# eth_10base-t1s_phy.net
KiCad netlist of a schematic drawn in Altium Designer
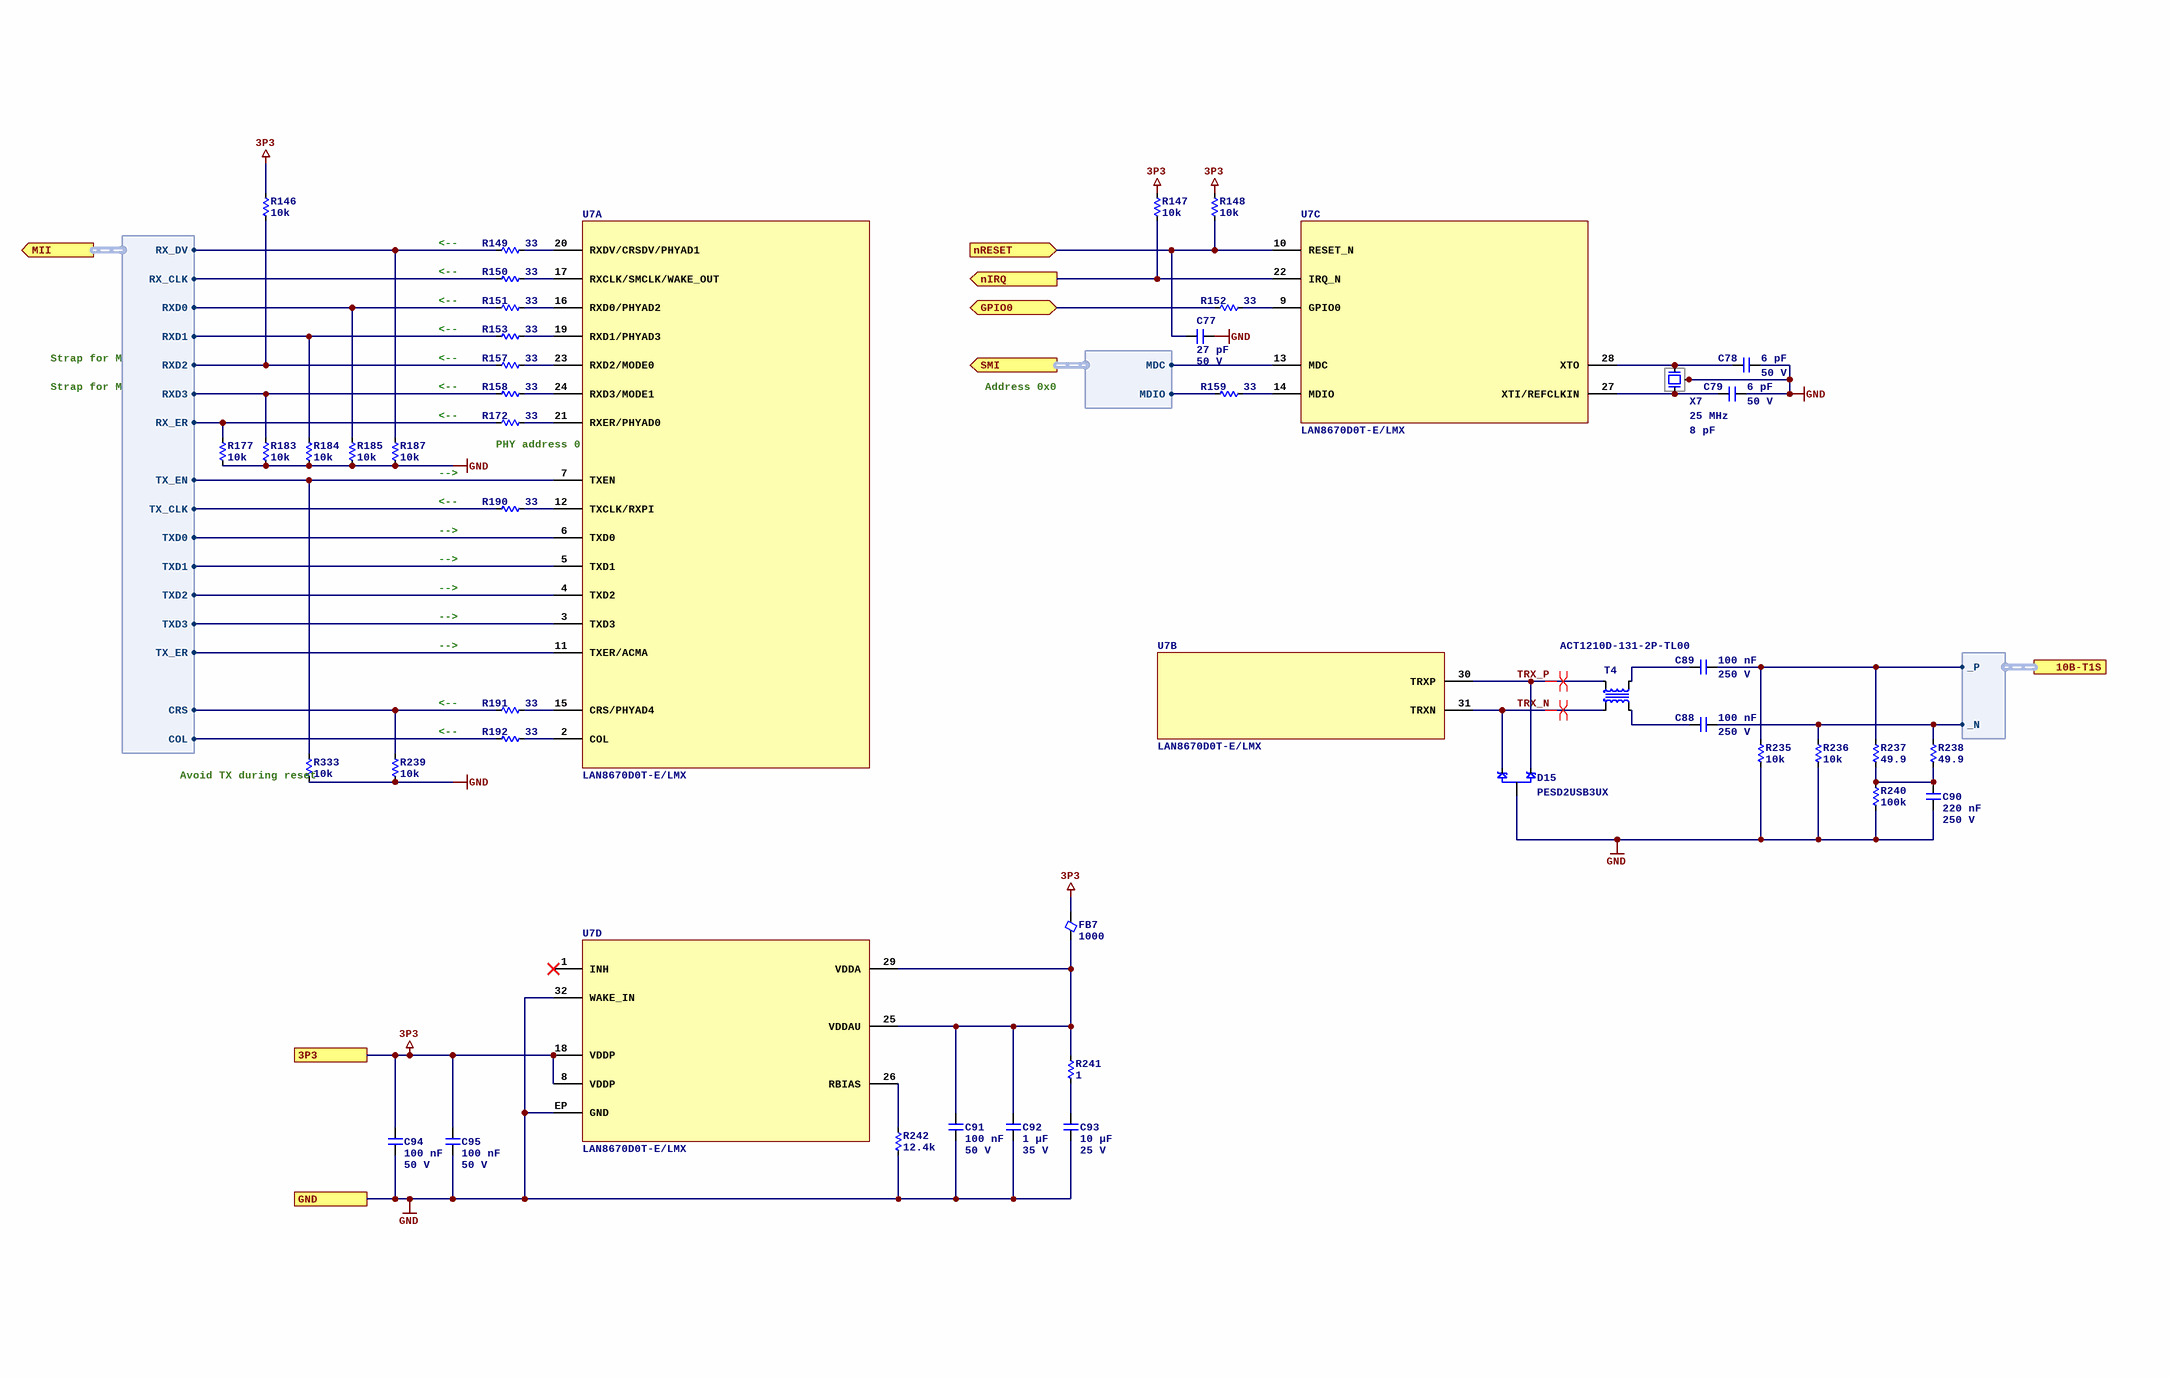
[diagram p0: eth_10base-t1s_phy.SchDoc]

(export (version "E")
  (design (tool "Eeschema 10.0.6"))
  (components
    (comp (ref "C77")
      (value "0402CG270J500NT")
      (footprint "C0402")
      (fields
        (field (name "CAPACITANCE") "27 pF")
        (field (name "MANUFACTURER") "FH(Guangdong Fenghua Advanced Tech)")
        (field (name "VOLTAGE RATING") "50 V")
      )
      (libsource (lib "database") (part "__template_cap"))
    )
    (comp (ref "C78")
      (value "0402CG6R0C500NT")
      (footprint "C0402")
      (fields
        (field (name "CAPACITANCE") "6 pF")
        (field (name "MANUFACTURER") "FH(Guangdong Fenghua Advanced Tech)")
        (field (name "VOLTAGE RATING") "50 V")
      )
      (libsource (lib "database") (part "__template_cap"))
    )
    (comp (ref "C79")
      (value "0402CG6R0C500NT")
      (footprint "C0402")
      (fields
        (field (name "CAPACITANCE") "6 pF")
        (field (name "MANUFACTURER") "FH(Guangdong Fenghua Advanced Tech)")
        (field (name "VOLTAGE RATING") "50 V")
      )
      (libsource (lib "database") (part "__template_cap"))
    )
    (comp (ref "C88")
      (value "FM31X104K251EEG")
      (footprint "C1206")
      (fields
        (field (name "CAPACITANCE") "100 nF")
        (field (name "MANUFACTURER") "PSA(Prosperity Dielectrics)")
        (field (name "VOLTAGE RATING") "250 V")
      )
      (libsource (lib "database") (part "__template_cap"))
    )
    (comp (ref "C89")
      (value "FM31X104K251EEG")
      (footprint "C1206")
      (fields
        (field (name "CAPACITANCE") "100 nF")
        (field (name "MANUFACTURER") "PSA(Prosperity Dielectrics)")
        (field (name "VOLTAGE RATING") "250 V")
      )
      (libsource (lib "database") (part "__template_cap"))
    )
    (comp (ref "C90")
      (value "FM32X224K251EEG")
      (footprint "C1210")
      (fields
        (field (name "CAPACITANCE") "220 nF")
        (field (name "MANUFACTURER") "PSA(Prosperity Dielectrics)")
        (field (name "VOLTAGE RATING") "250 V")
      )
      (libsource (lib "database") (part "__template_cap"))
    )
    (comp (ref "C91")
      (value "CL05B104KB54PNC")
      (footprint "C0402")
      (fields
        (field (name "CAPACITANCE") "100 nF")
        (field (name "MANUFACTURER") "Samsung Electro-Mechanics")
        (field (name "VOLTAGE RATING") "50 V")
      )
      (libsource (lib "database") (part "__template_cap"))
    )
    (comp (ref "C92")
      (value "GMK107AB7105KAHT")
      (footprint "C0603")
      (fields
        (field (name "CAPACITANCE") "1 µF")
        (field (name "MANUFACTURER") "Taiyo Yuden")
        (field (name "VOLTAGE RATING") "35 V")
      )
      (libsource (lib "database") (part "__template_cap"))
    )
    (comp (ref "C93")
      (value "CL21B106KAYQNNE")
      (footprint "C0805")
      (fields
        (field (name "CAPACITANCE") "10 µF")
        (field (name "MANUFACTURER") "Samsung Electro-Mechanics")
        (field (name "VOLTAGE RATING") "25 V")
      )
      (libsource (lib "database") (part "__template_cap"))
    )
    (comp (ref "C94")
      (value "CL05B104KB54PNC")
      (footprint "C0402")
      (fields
        (field (name "CAPACITANCE") "100 nF")
        (field (name "MANUFACTURER") "Samsung Electro-Mechanics")
        (field (name "VOLTAGE RATING") "50 V")
      )
      (libsource (lib "database") (part "__template_cap"))
    )
    (comp (ref "C95")
      (value "CL05B104KB54PNC")
      (footprint "C0402")
      (fields
        (field (name "CAPACITANCE") "100 nF")
        (field (name "MANUFACTURER") "Samsung Electro-Mechanics")
        (field (name "VOLTAGE RATING") "50 V")
      )
      (libsource (lib "database") (part "__template_cap"))
    )
    (comp (ref "D15")
      (value "PESD2USB3UX")
      (footprint "3SOT23")
      (description "DIODE ESD USB SOT-23")
      (fields (field (name "MANUFACTURER") "Nexperia USA Inc."))
      (libsource (lib "database") (part "PESD2USB3UX"))
    )
    (comp (ref "FB7")
      (value "HCB2012KF-102T10")
      (footprint "FB0805")
      (fields (field (name "MANUFACTURER") "TAI-TECH") (field (name "CURRENT RATING (MA)") "1000"))
      (libsource (lib "database") (part "__template_fb"))
    )
    (comp (ref "R146")
      (value "10k")
      (footprint "R0402")
      (fields
        (field (name "TOLERANCE") "1%")
        (field (name "MANUFACTURER PART NUMBER") "0402WGF1002TCE")
        (field (name "MANUFACTURER") "UNI-ROYAL(Uniroyal Elec)")
      )
      (libsource (lib "database") (part "__template_resistor"))
    )
    (comp (ref "R147")
      (value "10k")
      (footprint "R0402")
      (fields
        (field (name "TOLERANCE") "1%")
        (field (name "MANUFACTURER PART NUMBER") "0402WGF1002TCE")
        (field (name "MANUFACTURER") "UNI-ROYAL(Uniroyal Elec)")
      )
      (libsource (lib "database") (part "__template_resistor"))
    )
    (comp (ref "R148")
      (value "10k")
      (footprint "R0402")
      (fields
        (field (name "TOLERANCE") "1%")
        (field (name "MANUFACTURER PART NUMBER") "0402WGF1002TCE")
        (field (name "MANUFACTURER") "UNI-ROYAL(Uniroyal Elec)")
      )
      (libsource (lib "database") (part "__template_resistor"))
    )
    (comp (ref "R149")
      (value "33")
      (footprint "R0402")
      (fields
        (field (name "TOLERANCE") "1%")
        (field (name "MANUFACTURER PART NUMBER") "0402WGF330JTCE")
        (field (name "MANUFACTURER") "UNI-ROYAL(Uniroyal Elec)")
      )
      (libsource (lib "database") (part "__template_resistor"))
    )
    (comp (ref "R150")
      (value "33")
      (footprint "R0402")
      (fields
        (field (name "TOLERANCE") "1%")
        (field (name "MANUFACTURER PART NUMBER") "0402WGF330JTCE")
        (field (name "MANUFACTURER") "UNI-ROYAL(Uniroyal Elec)")
      )
      (libsource (lib "database") (part "__template_resistor"))
    )
    (comp (ref "R151")
      (value "33")
      (footprint "R0402")
      (fields
        (field (name "TOLERANCE") "1%")
        (field (name "MANUFACTURER PART NUMBER") "0402WGF330JTCE")
        (field (name "MANUFACTURER") "UNI-ROYAL(Uniroyal Elec)")
      )
      (libsource (lib "database") (part "__template_resistor"))
    )
    (comp (ref "R152")
      (value "33")
      (footprint "R0402")
      (fields
        (field (name "TOLERANCE") "1%")
        (field (name "MANUFACTURER PART NUMBER") "0402WGF330JTCE")
        (field (name "MANUFACTURER") "UNI-ROYAL(Uniroyal Elec)")
      )
      (libsource (lib "database") (part "__template_resistor"))
    )
    (comp (ref "R153")
      (value "33")
      (footprint "R0402")
      (fields
        (field (name "TOLERANCE") "1%")
        (field (name "MANUFACTURER PART NUMBER") "0402WGF330JTCE")
        (field (name "MANUFACTURER") "UNI-ROYAL(Uniroyal Elec)")
      )
      (libsource (lib "database") (part "__template_resistor"))
    )
    (comp (ref "R157")
      (value "33")
      (footprint "R0402")
      (fields
        (field (name "TOLERANCE") "1%")
        (field (name "MANUFACTURER PART NUMBER") "0402WGF330JTCE")
        (field (name "MANUFACTURER") "UNI-ROYAL(Uniroyal Elec)")
      )
      (libsource (lib "database") (part "__template_resistor"))
    )
    (comp (ref "R158")
      (value "33")
      (footprint "R0402")
      (fields
        (field (name "TOLERANCE") "1%")
        (field (name "MANUFACTURER PART NUMBER") "0402WGF330JTCE")
        (field (name "MANUFACTURER") "UNI-ROYAL(Uniroyal Elec)")
      )
      (libsource (lib "database") (part "__template_resistor"))
    )
    (comp (ref "R159")
      (value "33")
      (footprint "R0402")
      (fields
        (field (name "TOLERANCE") "1%")
        (field (name "MANUFACTURER PART NUMBER") "0402WGF330JTCE")
        (field (name "MANUFACTURER") "UNI-ROYAL(Uniroyal Elec)")
      )
      (libsource (lib "database") (part "__template_resistor"))
    )
    (comp (ref "R172")
      (value "33")
      (footprint "R0402")
      (fields
        (field (name "TOLERANCE") "1%")
        (field (name "MANUFACTURER PART NUMBER") "0402WGF330JTCE")
        (field (name "MANUFACTURER") "UNI-ROYAL(Uniroyal Elec)")
      )
      (libsource (lib "database") (part "__template_resistor"))
    )
    (comp (ref "R177")
      (value "10k")
      (footprint "R0402")
      (fields
        (field (name "TOLERANCE") "1%")
        (field (name "MANUFACTURER PART NUMBER") "0402WGF1002TCE")
        (field (name "MANUFACTURER") "UNI-ROYAL(Uniroyal Elec)")
      )
      (libsource (lib "database") (part "__template_resistor"))
    )
    (comp (ref "R183")
      (value "10k")
      (footprint "R0402")
      (fields
        (field (name "TOLERANCE") "1%")
        (field (name "MANUFACTURER PART NUMBER") "0402WGF1002TCE")
        (field (name "MANUFACTURER") "UNI-ROYAL(Uniroyal Elec)")
      )
      (libsource (lib "database") (part "__template_resistor"))
    )
    (comp (ref "R184")
      (value "10k")
      (footprint "R0402")
      (fields
        (field (name "TOLERANCE") "1%")
        (field (name "MANUFACTURER PART NUMBER") "0402WGF1002TCE")
        (field (name "MANUFACTURER") "UNI-ROYAL(Uniroyal Elec)")
      )
      (libsource (lib "database") (part "__template_resistor"))
    )
    (comp (ref "R185")
      (value "10k")
      (footprint "R0402")
      (fields
        (field (name "TOLERANCE") "1%")
        (field (name "MANUFACTURER PART NUMBER") "0402WGF1002TCE")
        (field (name "MANUFACTURER") "UNI-ROYAL(Uniroyal Elec)")
      )
      (libsource (lib "database") (part "__template_resistor"))
    )
    (comp (ref "R187")
      (value "10k")
      (footprint "R0402")
      (fields
        (field (name "TOLERANCE") "1%")
        (field (name "MANUFACTURER PART NUMBER") "0402WGF1002TCE")
        (field (name "MANUFACTURER") "UNI-ROYAL(Uniroyal Elec)")
      )
      (libsource (lib "database") (part "__template_resistor"))
    )
    (comp (ref "R190")
      (value "33")
      (footprint "R0402")
      (fields
        (field (name "TOLERANCE") "1%")
        (field (name "MANUFACTURER PART NUMBER") "0402WGF330JTCE")
        (field (name "MANUFACTURER") "UNI-ROYAL(Uniroyal Elec)")
      )
      (libsource (lib "database") (part "__template_resistor"))
    )
    (comp (ref "R191")
      (value "33")
      (footprint "R0402")
      (fields
        (field (name "TOLERANCE") "1%")
        (field (name "MANUFACTURER PART NUMBER") "0402WGF330JTCE")
        (field (name "MANUFACTURER") "UNI-ROYAL(Uniroyal Elec)")
      )
      (libsource (lib "database") (part "__template_resistor"))
    )
    (comp (ref "R192")
      (value "33")
      (footprint "R0402")
      (fields
        (field (name "TOLERANCE") "1%")
        (field (name "MANUFACTURER PART NUMBER") "0402WGF330JTCE")
        (field (name "MANUFACTURER") "UNI-ROYAL(Uniroyal Elec)")
      )
      (libsource (lib "database") (part "__template_resistor"))
    )
    (comp (ref "R235")
      (value "10k")
      (footprint "R1206")
      (fields
        (field (name "TOLERANCE") "1%")
        (field (name "MANUFACTURER PART NUMBER") "1206W4F1002T5E")
        (field (name "MANUFACTURER") "UNI-ROYAL(Uniroyal Elec)")
      )
      (libsource (lib "database") (part "__template_resistor"))
    )
    (comp (ref "R236")
      (value "10k")
      (footprint "R1206")
      (fields
        (field (name "TOLERANCE") "1%")
        (field (name "MANUFACTURER PART NUMBER") "1206W4F1002T5E")
        (field (name "MANUFACTURER") "UNI-ROYAL(Uniroyal Elec)")
      )
      (libsource (lib "database") (part "__template_resistor"))
    )
    (comp (ref "R237")
      (value "49.9")
      (footprint "R1206")
      (fields
        (field (name "TOLERANCE") "1%")
        (field (name "MANUFACTURER PART NUMBER") "FRC1206F49R9TS")
        (field (name "MANUFACTURER") "FOJAN")
      )
      (libsource (lib "database") (part "__template_resistor"))
    )
    (comp (ref "R238")
      (value "49.9")
      (footprint "R1206")
      (fields
        (field (name "TOLERANCE") "1%")
        (field (name "MANUFACTURER PART NUMBER") "FRC1206F49R9TS")
        (field (name "MANUFACTURER") "FOJAN")
      )
      (libsource (lib "database") (part "__template_resistor"))
    )
    (comp (ref "R239")
      (value "10k")
      (footprint "R0402")
      (fields
        (field (name "TOLERANCE") "1%")
        (field (name "MANUFACTURER PART NUMBER") "0402WGF1002TCE")
        (field (name "MANUFACTURER") "UNI-ROYAL(Uniroyal Elec)")
      )
      (libsource (lib "database") (part "__template_resistor"))
    )
    (comp (ref "R240")
      (value "100k")
      (footprint "R1206")
      (fields
        (field (name "TOLERANCE") "1%")
        (field (name "MANUFACTURER PART NUMBER") "1206W4F1003T5E")
        (field (name "MANUFACTURER") "UNI-ROYAL(Uniroyal Elec)")
      )
      (libsource (lib "database") (part "__template_resistor"))
    )
    (comp (ref "R241")
      (value "1")
      (footprint "R0402")
      (fields
        (field (name "TOLERANCE") "1%")
        (field (name "MANUFACTURER PART NUMBER") "CRCW04021R00FKED")
        (field (name "MANUFACTURER") "Vishay Intertech")
      )
      (libsource (lib "database") (part "__template_resistor"))
    )
    (comp (ref "R242")
      (value "12.4k")
      (footprint "R0402")
      (fields
        (field (name "TOLERANCE") "0.5%")
        (field (name "MANUFACTURER PART NUMBER") "0402WGD1242TCE")
        (field (name "MANUFACTURER") "UNI-ROYAL(Uniroyal Elec)")
      )
      (libsource (lib "database") (part "__template_resistor"))
    )
    (comp (ref "R333")
      (value "10k")
      (footprint "R0402")
      (fields
        (field (name "TOLERANCE") "1%")
        (field (name "MANUFACTURER PART NUMBER") "0402WGF1002TCE")
        (field (name "MANUFACTURER") "UNI-ROYAL(Uniroyal Elec)")
      )
      (libsource (lib "database") (part "__template_resistor"))
    )
    (comp (ref "T4")
      (value "ACT1210D-131-2P-TL00")
      (footprint "CHOKE_ACT1210D-131-2P-TL00")
      (description "130 µH @ 100 kHz 2 Line Common Mode Choke Surface Mount 6.7 kOhms @ 10 MHz 115mA DCR 3.5Ohm")
      (fields (field (name "MANUFACTURER") "TDK Corporation"))
      (libsource (lib "database") (part "__template_transformer"))
    )
    (comp (ref "U7")
      (value "LAN8670D0T-E/LMX")
      (footprint "QFN50P500X500X90-32N")
      (description "10BASE-T1S PHY WITH MII/RMII \"1/1 Transceiver Full, Half Ethernet 32-VQFN (5x5)\"")
      (fields (field (name "MANUFACTURER") "Microchip"))
      (libsource (lib "database") (part "LAN8670D0T-E/LMX"))
    )
    (comp (ref "X7")
      (value "ABM11W-25.0000MHZ-8-D1X-T3")
      (footprint "4_SMD_2.0X1.6MM")
      (description "25 MHz ±10ppm Crystal 8pF 50 Ohms 4-SMD, No Lead")
      (fields
        (field (name "MANUFACTURER") "Abracon LLC")
        (field (name "FREQUENCY") "25 MHz")
        (field (name "CAPACITANCE") "8 pF")
      )
      (libsource (lib "database") (part "__template_crystal_4pin"))
    )
  )
  (nets
    (net (code "4") (name "/COL") (class "Default") (node (ref "R192") (pin "2") (pintype "passive")))
    (net (code "5") (name "/CRS") (class "Default")
      (node (ref "R191") (pin "2") (pintype "passive"))
      (node (ref "R239") (pin "1") (pintype "passive"))
    )
    (net (code "6") (name "/GPIO0") (class "Default") (node (ref "R152") (pin "2") (pintype "passive")))
    (net (code "7") (name "/MDC") (class "Default")
      (node (ref "U7") (pin "13") (pinfunction "MDC_13") (pintype "passive"))
    )
    (net (code "8") (name "/MDIO") (class "Default") (node (ref "R159") (pin "2") (pintype "passive")))
    (net (code "9") (name "/RXD0") (class "Default")
      (node (ref "R151") (pin "2") (pintype "passive"))
      (node (ref "R185") (pin "1") (pintype "passive"))
    )
    (net (code "10") (name "/RXD1") (class "Default")
      (node (ref "R153") (pin "2") (pintype "passive"))
      (node (ref "R184") (pin "1") (pintype "passive"))
    )
    (net (code "11") (name "/RXD2") (class "Default")
      (node (ref "R146") (pin "2") (pintype "passive"))
      (node (ref "R157") (pin "2") (pintype "passive"))
    )
    (net (code "12") (name "/RXD3") (class "Default")
      (node (ref "R158") (pin "2") (pintype "passive"))
      (node (ref "R183") (pin "1") (pintype "passive"))
    )
    (net (code "13") (name "/RX_CLK") (class "Default") (node (ref "R150") (pin "2") (pintype "passive")))
    (net (code "14") (name "/RX_DV") (class "Default")
      (node (ref "R149") (pin "2") (pintype "passive"))
      (node (ref "R187") (pin "1") (pintype "passive"))
    )
    (net (code "15") (name "/RX_ER") (class "Default")
      (node (ref "R172") (pin "2") (pintype "passive"))
      (node (ref "R177") (pin "1") (pintype "passive"))
    )
    (net (code "16") (name "/TRX_N") (class "Default")
      (node (ref "D15") (pin "1") (pintype "passive"))
      (node (ref "T4") (pin "1") (pintype "passive"))
      (node (ref "U7") (pin "31") (pinfunction "TRXN_31") (pintype "passive"))
    )
    (net (code "17") (name "/TRX_P") (class "Default")
      (node (ref "D15") (pin "2") (pintype "passive"))
      (node (ref "T4") (pin "2") (pintype "passive"))
      (node (ref "U7") (pin "30") (pinfunction "TRXP_30") (pintype "passive"))
    )
    (net (code "18") (name "/TXD0") (class "Default")
      (node (ref "U7") (pin "6") (pinfunction "TXD0_6") (pintype "passive"))
    )
    (net (code "19") (name "/TXD1") (class "Default")
      (node (ref "U7") (pin "5") (pinfunction "TXD1_5") (pintype "passive"))
    )
    (net (code "20") (name "/TXD2") (class "Default")
      (node (ref "U7") (pin "4") (pinfunction "TXD2_4") (pintype "passive"))
    )
    (net (code "21") (name "/TXD3") (class "Default")
      (node (ref "U7") (pin "3") (pinfunction "TXD3_3") (pintype "passive"))
    )
    (net (code "22") (name "/TX_CLK") (class "Default") (node (ref "R190") (pin "2") (pintype "passive")))
    (net (code "23") (name "/TX_EN") (class "Default")
      (node (ref "R333") (pin "1") (pintype "passive"))
      (node (ref "U7") (pin "7") (pinfunction "TXEN_7") (pintype "passive"))
    )
    (net (code "24") (name "/TX_ER") (class "Default")
      (node (ref "U7") (pin "11") (pinfunction "TXER/ACMA_11") (pintype "passive"))
    )
    (net (code "25") (name "/_N") (class "Default")
      (node (ref "C88") (pin "2") (pintype "passive"))
      (node (ref "R236") (pin "1") (pintype "passive"))
      (node (ref "R238") (pin "1") (pintype "passive"))
    )
    (net (code "26") (name "/_P") (class "Default")
      (node (ref "C89") (pin "2") (pintype "passive"))
      (node (ref "R235") (pin "1") (pintype "passive"))
      (node (ref "R237") (pin "1") (pintype "passive"))
    )
    (net (code "27") (name "/nIRQ") (class "Default")
      (node (ref "R147") (pin "2") (pintype "passive"))
      (node (ref "U7") (pin "22") (pinfunction "IRQ_N_22") (pintype "passive"))
    )
    (net (code "28") (name "/nRESET") (class "Default")
      (node (ref "C77") (pin "1") (pintype "passive"))
      (node (ref "R148") (pin "2") (pintype "passive"))
      (node (ref "U7") (pin "10") (pinfunction "RESET_N_10") (pintype "passive"))
    )
    (net (code "32") (name "3P3") (class "Default")
      (node (ref "C94") (pin "1") (pintype "passive"))
      (node (ref "C95") (pin "1") (pintype "passive"))
      (node (ref "FB7") (pin "2") (pintype "passive"))
      (node (ref "R146") (pin "1") (pintype "passive"))
      (node (ref "R147") (pin "1") (pintype "passive"))
      (node (ref "R148") (pin "1") (pintype "passive"))
      (node (ref "U7") (pin "18") (pinfunction "VDDP_18") (pintype "passive"))
      (node (ref "U7") (pin "8") (pinfunction "VDDP_8") (pintype "passive"))
    )
    (net (code "33") (name "GND") (class "Default")
      (node (ref "C77") (pin "2") (pintype "passive"))
      (node (ref "C78") (pin "2") (pintype "passive"))
      (node (ref "C79") (pin "2") (pintype "passive"))
      (node (ref "C90") (pin "2") (pintype "passive"))
      (node (ref "C91") (pin "2") (pintype "passive"))
      (node (ref "C92") (pin "2") (pintype "passive"))
      (node (ref "C93") (pin "2") (pintype "passive"))
      (node (ref "C94") (pin "2") (pintype "passive"))
      (node (ref "C95") (pin "2") (pintype "passive"))
      (node (ref "D15") (pin "3") (pintype "passive"))
      (node (ref "R177") (pin "2") (pintype "passive"))
      (node (ref "R183") (pin "2") (pintype "passive"))
      (node (ref "R184") (pin "2") (pintype "passive"))
      (node (ref "R185") (pin "2") (pintype "passive"))
      (node (ref "R187") (pin "2") (pintype "passive"))
      (node (ref "R235") (pin "2") (pintype "passive"))
      (node (ref "R236") (pin "2") (pintype "passive"))
      (node (ref "R239") (pin "2") (pintype "passive"))
      (node (ref "R240") (pin "2") (pintype "passive"))
      (node (ref "R242") (pin "2") (pintype "passive"))
      (node (ref "R333") (pin "2") (pintype "passive"))
      (node (ref "U7") (pin "32") (pinfunction "WAKE_IN_32") (pintype "passive"))
      (node (ref "U7") (pin "EP") (pinfunction "GND_EP") (pintype "passive"))
      (node (ref "X7") (pin "2") (pinfunction "2_2") (pintype "passive"))
      (node (ref "X7") (pin "4") (pinfunction "4_4") (pintype "passive"))
    )
    (net (code "34") (name "Net-(C88-Pad1)") (class "Default")
      (node (ref "C88") (pin "1") (pintype "passive"))
      (node (ref "T4") (pin "4") (pintype "passive"))
    )
    (net (code "35") (name "Net-(C89-Pad1)") (class "Default")
      (node (ref "C89") (pin "1") (pintype "passive"))
      (node (ref "T4") (pin "3") (pintype "passive"))
    )
    (net (code "36") (name "Net-(C90-Pad1)") (class "Default")
      (node (ref "C90") (pin "1") (pintype "passive"))
      (node (ref "R237") (pin "2") (pintype "passive"))
      (node (ref "R238") (pin "2") (pintype "passive"))
      (node (ref "R240") (pin "1") (pintype "passive"))
    )
    (net (code "37") (name "Net-(C93-Pad1)") (class "Default")
      (node (ref "C93") (pin "1") (pintype "passive"))
      (node (ref "R241") (pin "1") (pintype "passive"))
    )
    (net (code "38") (name "Net-(U7A-COL)") (class "Default")
      (node (ref "R192") (pin "1") (pintype "passive"))
      (node (ref "U7") (pin "2") (pinfunction "COL_2") (pintype "passive"))
    )
    (net (code "39") (name "Net-(U7A-CRS{slash}PHYAD4)") (class "Default")
      (node (ref "R191") (pin "1") (pintype "passive"))
      (node (ref "U7") (pin "15") (pinfunction "CRS/PHYAD4_15") (pintype "passive"))
    )
    (net (code "40") (name "Net-(U7A-RXCLK{slash}SMCLK{slash}WAKE_OUT)") (class "Default")
      (node (ref "R150") (pin "1") (pintype "passive"))
      (node (ref "U7") (pin "17") (pinfunction "RXCLK/SMCLK/WAKE_OUT_17") (pintype "passive"))
    )
    (net (code "41") (name "Net-(U7A-RXD0{slash}PHYAD2)") (class "Default")
      (node (ref "R151") (pin "1") (pintype "passive"))
      (node (ref "U7") (pin "16") (pinfunction "RXD0/PHYAD2_16") (pintype "passive"))
    )
    (net (code "42") (name "Net-(U7A-RXD1{slash}PHYAD3)") (class "Default")
      (node (ref "R153") (pin "1") (pintype "passive"))
      (node (ref "U7") (pin "19") (pinfunction "RXD1/PHYAD3_19") (pintype "passive"))
    )
    (net (code "43") (name "Net-(U7A-RXD2{slash}MODE0)") (class "Default")
      (node (ref "R157") (pin "1") (pintype "passive"))
      (node (ref "U7") (pin "23") (pinfunction "RXD2/MODE0_23") (pintype "passive"))
    )
    (net (code "44") (name "Net-(U7A-RXD3{slash}MODE1)") (class "Default")
      (node (ref "R158") (pin "1") (pintype "passive"))
      (node (ref "U7") (pin "24") (pinfunction "RXD3/MODE1_24") (pintype "passive"))
    )
    (net (code "45") (name "Net-(U7A-RXDV{slash}CRSDV{slash}PHYAD1)") (class "Default")
      (node (ref "R149") (pin "1") (pintype "passive"))
      (node (ref "U7") (pin "20") (pinfunction "RXDV/CRSDV/PHYAD1_20") (pintype "passive"))
    )
    (net (code "46") (name "Net-(U7A-RXER{slash}PHYAD0)") (class "Default")
      (node (ref "R172") (pin "1") (pintype "passive"))
      (node (ref "U7") (pin "21") (pinfunction "RXER/PHYAD0_21") (pintype "passive"))
    )
    (net (code "47") (name "Net-(U7A-TXCLK{slash}RXPI)") (class "Default")
      (node (ref "R190") (pin "1") (pintype "passive"))
      (node (ref "U7") (pin "12") (pinfunction "TXCLK/RXPI_12") (pintype "passive"))
    )
    (net (code "48") (name "Net-(U7C-GPIO0)") (class "Default")
      (node (ref "R152") (pin "1") (pintype "passive"))
      (node (ref "U7") (pin "9") (pinfunction "GPIO0_9") (pintype "passive"))
    )
    (net (code "49") (name "Net-(U7C-MDIO)") (class "Default")
      (node (ref "R159") (pin "1") (pintype "passive"))
      (node (ref "U7") (pin "14") (pinfunction "MDIO_14") (pintype "passive"))
    )
    (net (code "50") (name "Net-(U7C-XTI{slash}REFCLKIN)") (class "Default")
      (node (ref "C79") (pin "1") (pintype "passive"))
      (node (ref "U7") (pin "27") (pinfunction "XTI/REFCLKIN_27") (pintype "passive"))
      (node (ref "X7") (pin "1") (pinfunction "1_1") (pintype "passive"))
    )
    (net (code "51") (name "Net-(U7C-XTO)") (class "Default")
      (node (ref "C78") (pin "1") (pintype "passive"))
      (node (ref "U7") (pin "28") (pinfunction "XTO_28") (pintype "passive"))
      (node (ref "X7") (pin "3") (pinfunction "3_3") (pintype "passive"))
    )
    (net (code "52") (name "Net-(U7D-RBIAS)") (class "Default")
      (node (ref "R242") (pin "1") (pintype "passive"))
      (node (ref "U7") (pin "26") (pinfunction "RBIAS_26") (pintype "passive"))
    )
    (net (code "53") (name "Net-(U7D-VDDA)") (class "Default")
      (node (ref "C91") (pin "1") (pintype "passive"))
      (node (ref "C92") (pin "1") (pintype "passive"))
      (node (ref "FB7") (pin "1") (pintype "passive"))
      (node (ref "R241") (pin "2") (pintype "passive"))
      (node (ref "U7") (pin "25") (pinfunction "VDDAU_25") (pintype "passive"))
      (node (ref "U7") (pin "29") (pinfunction "VDDA_29") (pintype "passive"))
    )
    (net (code "54") (name "unconnected-(U7D-INH-Pad1)") (class "Default")
      (node (ref "U7") (pin "1") (pinfunction "INH_1") (pintype "passive+no_connect"))
    )
  )
)
